# FuzzEffect.net
KiCad netlist of a schematic drawn in EasyEDA
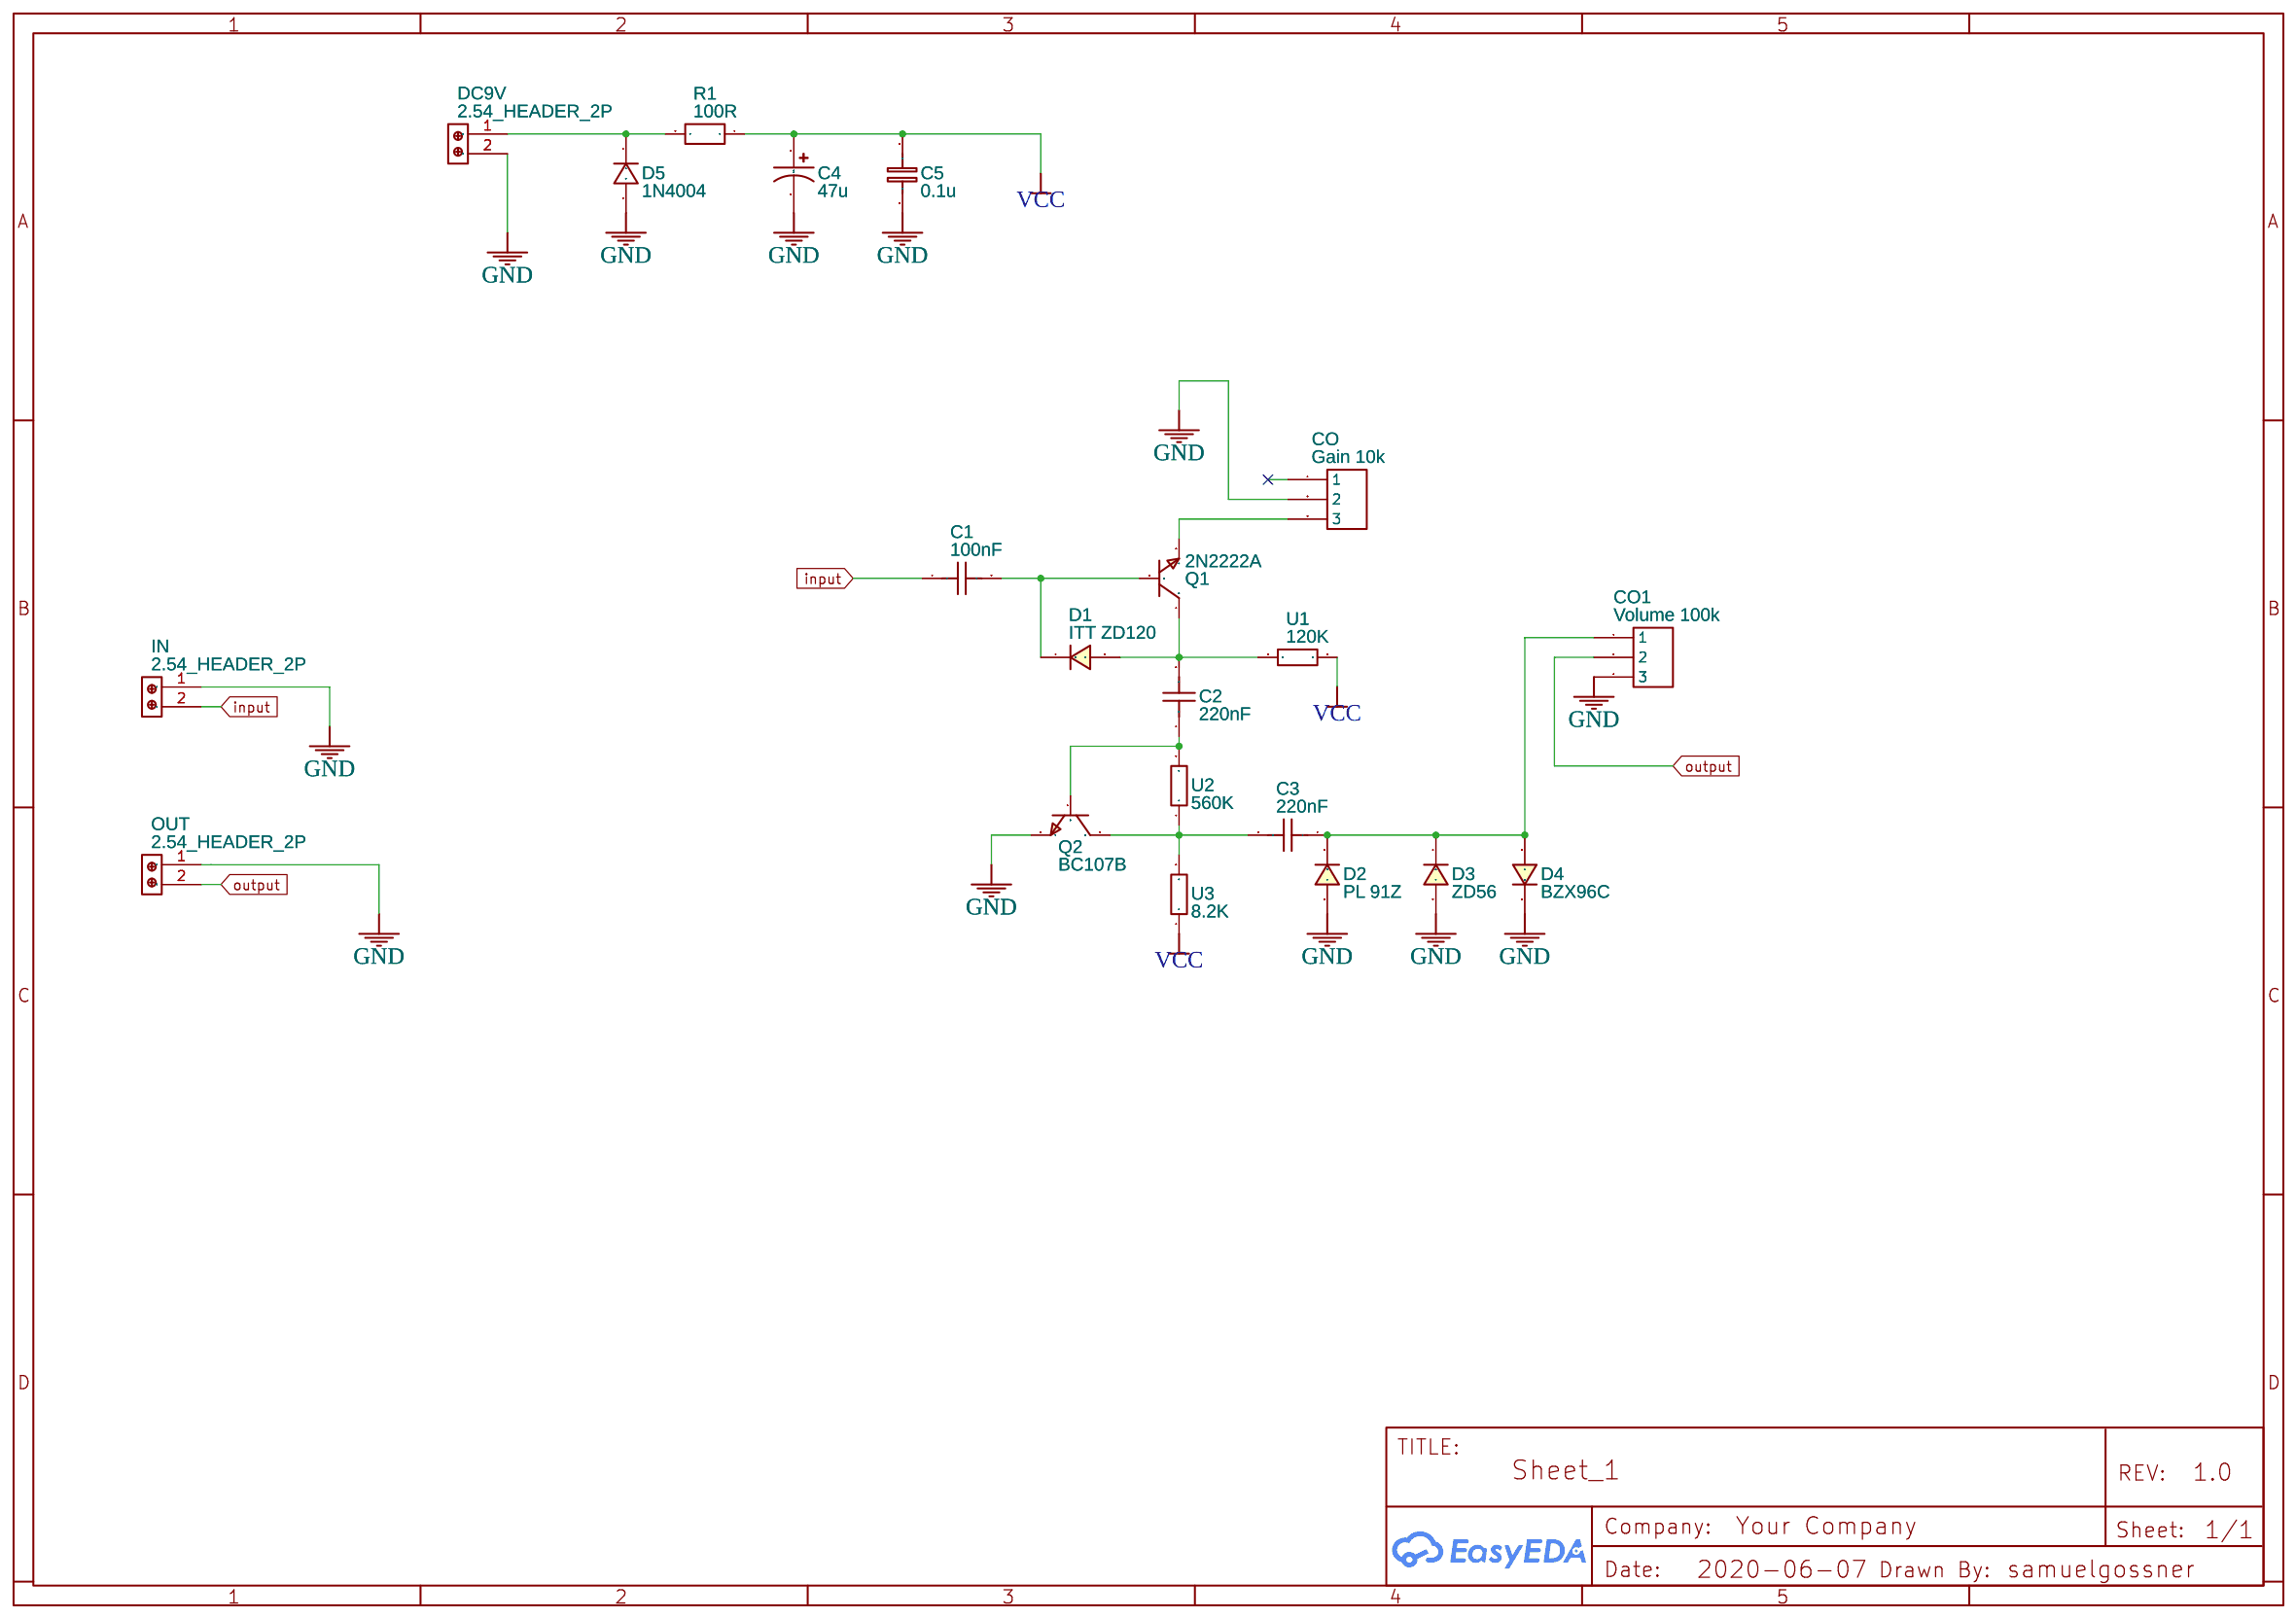
[diagram p0: schematic sheet]

(export (version "E")
  (design (tool "Eeschema 10.0.6"))
  (components
    (comp (ref "C1")
      (value "100nF")
      (fields
        (field (name "BOM_Manufacturer Part") "0805B104K101")
        (field (name "BOM_Supplier Part") "C77456")
      )
      (libsource (lib "") (part "0805B104K101"))
    )
    (comp (ref "C2")
      (value "220nF")
      (fields
        (field (name "BOM_Manufacturer Part") "1206B224K101")
        (field (name "BOM_Supplier Part") "C77515")
      )
      (libsource (lib "") (part "1206B224K101"))
    )
    (comp (ref "C3")
      (value "220nF")
      (fields
        (field (name "BOM_Manufacturer Part") "1206B224K101")
        (field (name "BOM_Supplier Part") "C77515")
      )
      (libsource (lib "") (part "1206B224K101_1"))
    )
    (comp (ref "C4") (value "47u") (libsource (lib "") (part "C_Tan_SMD_A_US")))
    (comp (ref "C5") (value "0.1u") (libsource (lib "") (part "C_0603_EU")))
    (comp (ref "CO")
      (value "Gain 10k")
      (fields
        (field (name "BOM_Manufacturer Part") "Header2.54mm 1*3P")
        (field (name "BOM_Supplier Part") "C49257")
      )
      (libsource (lib "") (part "Header2.54mm 1*3P copy"))
    )
    (comp (ref "CO1")
      (value "Volume 100k")
      (fields
        (field (name "BOM_Manufacturer Part") "Header2.54mm 1*3P")
        (field (name "BOM_Supplier Part") "C49257")
      )
      (libsource (lib "") (part "Header2.54mm 1*3P copy"))
    )
    (comp (ref "D1")
      (value "ITT ZD120")
      (fields (field (name "BOM_Manufacturer Part") "FR107") (field (name "BOM_Supplier Part") "C84243"))
      (libsource (lib "") (part "FR107-C84243_1"))
    )
    (comp (ref "D2")
      (value "PL 91Z")
      (fields (field (name "BOM_Manufacturer Part") "FR107") (field (name "BOM_Supplier Part") "C84243"))
      (libsource (lib "") (part "FR107-C84243"))
    )
    (comp (ref "D3")
      (value "ZD56")
      (fields (field (name "BOM_Manufacturer Part") "FR107") (field (name "BOM_Supplier Part") "C84243"))
      (libsource (lib "") (part "FR107-C84243"))
    )
    (comp (ref "D4")
      (value "BZX96C")
      (fields (field (name "BOM_Manufacturer Part") "FR107") (field (name "BOM_Supplier Part") "C84243"))
      (libsource (lib "") (part "FR107-C84243_2"))
    )
    (comp (ref "D5")
      (value "1N4004")
      (fields (field (name "BOM_Manufacturer Part") "1N4148W") (field (name "BOM_Supplier Part") "C129216"))
      (libsource (lib "") (part "1N4148W"))
    )
    (comp (ref "DC9V")
      (value "2.54_HEADER_2P")
      (fields (field (name "BOM_Supplier Part") "undefined"))
      (libsource (lib "") (part "2.54_HEADER_2P_1"))
    )
    (comp (ref "IN")
      (value "2.54_HEADER_2P")
      (fields (field (name "BOM_Supplier Part") "undefined"))
      (libsource (lib "") (part "2.54_HEADER_2P"))
    )
    (comp (ref "OUT")
      (value "2.54_HEADER_2P")
      (fields (field (name "BOM_Supplier Part") "undefined"))
      (libsource (lib "") (part "2.54_HEADER_2P_2"))
    )
    (comp (ref "Q1")
      (value "2N2222A")
      (fields (field (name "BOM_Supplier Part") "C358533"))
      (libsource (lib "") (part "2N2222A_1"))
    )
    (comp (ref "Q2")
      (value "BC107B")
      (fields (field (name "BOM_Manufacturer Part") "2N2222A") (field (name "BOM_Supplier Part") "C358533"))
      (libsource (lib "") (part "2N2222A"))
    )
    (comp (ref "R1") (value "100R") (libsource (lib "") (part "R_0603_EU")))
    (comp (ref "U1")
      (value "120K")
      (fields
        (field (name "BOM_Manufacturer Part") "MElF-MFR02041/4WS120KΩFT50")
        (field (name "BOM_Supplier Part") "C265587")
      )
      (libsource (lib "") (part "MELF-MFR02041/4WS120KΩFT50"))
    )
    (comp (ref "U2")
      (value "560K")
      (fields
        (field (name "BOM_Manufacturer Part") "MElF-MFR02041/4WS560KΩFT50")
        (field (name "BOM_Supplier Part") "C265637")
      )
      (libsource (lib "") (part "MELF-MFR02041/4WS560KΩFT50"))
    )
    (comp (ref "U3")
      (value "8.2K")
      (fields
        (field (name "BOM_Manufacturer Part") "MElF-MFR02041/4WS8.2KΩFT50")
        (field (name "BOM_Supplier Part") "C265602")
      )
      (libsource (lib "") (part "MELF-MFR02041/4WS8.2KΩFT50"))
    )
  )
  (nets
    (net (code "1") (name "GND") (class "Default")
      (node (ref "C4") (pin "2") (pinfunction "2_2") (pintype "unspecified"))
      (node (ref "C5") (pin "1") (pinfunction "1_1") (pintype "unspecified"))
      (node (ref "CO") (pin "2") (pinfunction "2_2") (pintype "input"))
      (node (ref "CO1") (pin "3") (pinfunction "3_3") (pintype "input"))
      (node (ref "D2") (pin "2") (pinfunction "A_2") (pintype "unspecified"))
      (node (ref "D3") (pin "2") (pinfunction "A_2") (pintype "unspecified"))
      (node (ref "D4") (pin "1") (pinfunction "C_1") (pintype "unspecified"))
      (node (ref "D5") (pin "2") (pinfunction "2_2") (pintype "unspecified"))
      (node (ref "DC9V") (pin "2") (pinfunction "2_2") (pintype "unspecified"))
      (node (ref "IN") (pin "1") (pinfunction "1_1") (pintype "unspecified"))
      (node (ref "OUT") (pin "1") (pinfunction "1_1") (pintype "unspecified"))
      (node (ref "Q2") (pin "3") (pinfunction "E_3") (pintype "unspecified"))
    )
    (net (code "2") (name "Net-(D1-A)") (class "Default")
      (node (ref "C2") (pin "2") (pinfunction "2_2") (pintype "unspecified"))
      (node (ref "D1") (pin "2") (pinfunction "A_2") (pintype "unspecified"))
      (node (ref "Q1") (pin "1") (pinfunction "C_1") (pintype "unspecified"))
      (node (ref "U1") (pin "1") (pinfunction "1_1") (pintype "unspecified"))
    )
    (net (code "3") (name "Net-(D1-C)") (class "Default")
      (node (ref "C1") (pin "2") (pinfunction "2_2") (pintype "unspecified"))
      (node (ref "D1") (pin "1") (pinfunction "C_1") (pintype "unspecified"))
      (node (ref "Q1") (pin "2") (pinfunction "B_2") (pintype "unspecified"))
    )
    (net (code "4") (name "Net-(D2-C)") (class "Default")
      (node (ref "C3") (pin "1") (pinfunction "1_1") (pintype "unspecified"))
      (node (ref "CO1") (pin "1") (pinfunction "1_1") (pintype "input"))
      (node (ref "D2") (pin "1") (pinfunction "C_1") (pintype "unspecified"))
      (node (ref "D3") (pin "1") (pinfunction "C_1") (pintype "unspecified"))
      (node (ref "D4") (pin "2") (pinfunction "A_2") (pintype "unspecified"))
    )
    (net (code "5") (name "Net-(D5-Pad1)") (class "Default")
      (node (ref "D5") (pin "1") (pinfunction "1_1") (pintype "unspecified"))
      (node (ref "DC9V") (pin "1") (pinfunction "1_1") (pintype "unspecified"))
      (node (ref "R1") (pin "2") (pinfunction "2_2") (pintype "unspecified"))
    )
    (net (code "6") (name "Net-(Q1-E)") (class "Default")
      (node (ref "CO") (pin "3") (pinfunction "3_3") (pintype "input"))
      (node (ref "Q1") (pin "3") (pinfunction "E_3") (pintype "unspecified"))
    )
    (net (code "7") (name "Net-(Q2-B)") (class "Default")
      (node (ref "C2") (pin "1") (pinfunction "1_1") (pintype "unspecified"))
      (node (ref "Q2") (pin "2") (pinfunction "B_2") (pintype "unspecified"))
      (node (ref "U2") (pin "2") (pinfunction "2_2") (pintype "unspecified"))
    )
    (net (code "8") (name "Net-(Q2-C)") (class "Default")
      (node (ref "C3") (pin "2") (pinfunction "2_2") (pintype "unspecified"))
      (node (ref "Q2") (pin "1") (pinfunction "C_1") (pintype "unspecified"))
      (node (ref "U2") (pin "1") (pinfunction "1_1") (pintype "unspecified"))
      (node (ref "U3") (pin "2") (pinfunction "2_2") (pintype "unspecified"))
    )
    (net (code "9") (name "VCC") (class "Default")
      (node (ref "C4") (pin "1") (pinfunction "1_1") (pintype "unspecified"))
      (node (ref "C5") (pin "2") (pinfunction "2_2") (pintype "unspecified"))
      (node (ref "R1") (pin "1") (pinfunction "1_1") (pintype "unspecified"))
      (node (ref "U1") (pin "2") (pinfunction "2_2") (pintype "unspecified"))
      (node (ref "U3") (pin "1") (pinfunction "1_1") (pintype "unspecified"))
    )
    (net (code "10") (name "input") (class "Default")
      (node (ref "C1") (pin "1") (pinfunction "1_1") (pintype "unspecified"))
      (node (ref "IN") (pin "2") (pinfunction "2_2") (pintype "unspecified"))
    )
    (net (code "11") (name "output") (class "Default")
      (node (ref "CO1") (pin "2") (pinfunction "2_2") (pintype "input"))
      (node (ref "OUT") (pin "2") (pinfunction "2_2") (pintype "unspecified"))
    )
    (net (code "12") (name "unconnected-(CO-Pad1)") (class "Default")
      (node (ref "CO") (pin "1") (pinfunction "1_1") (pintype "input+no_connect"))
    )
  )
)
